# CAN_-_STM32F4.net
KiCad netlist of a schematic drawn in Altium Designer
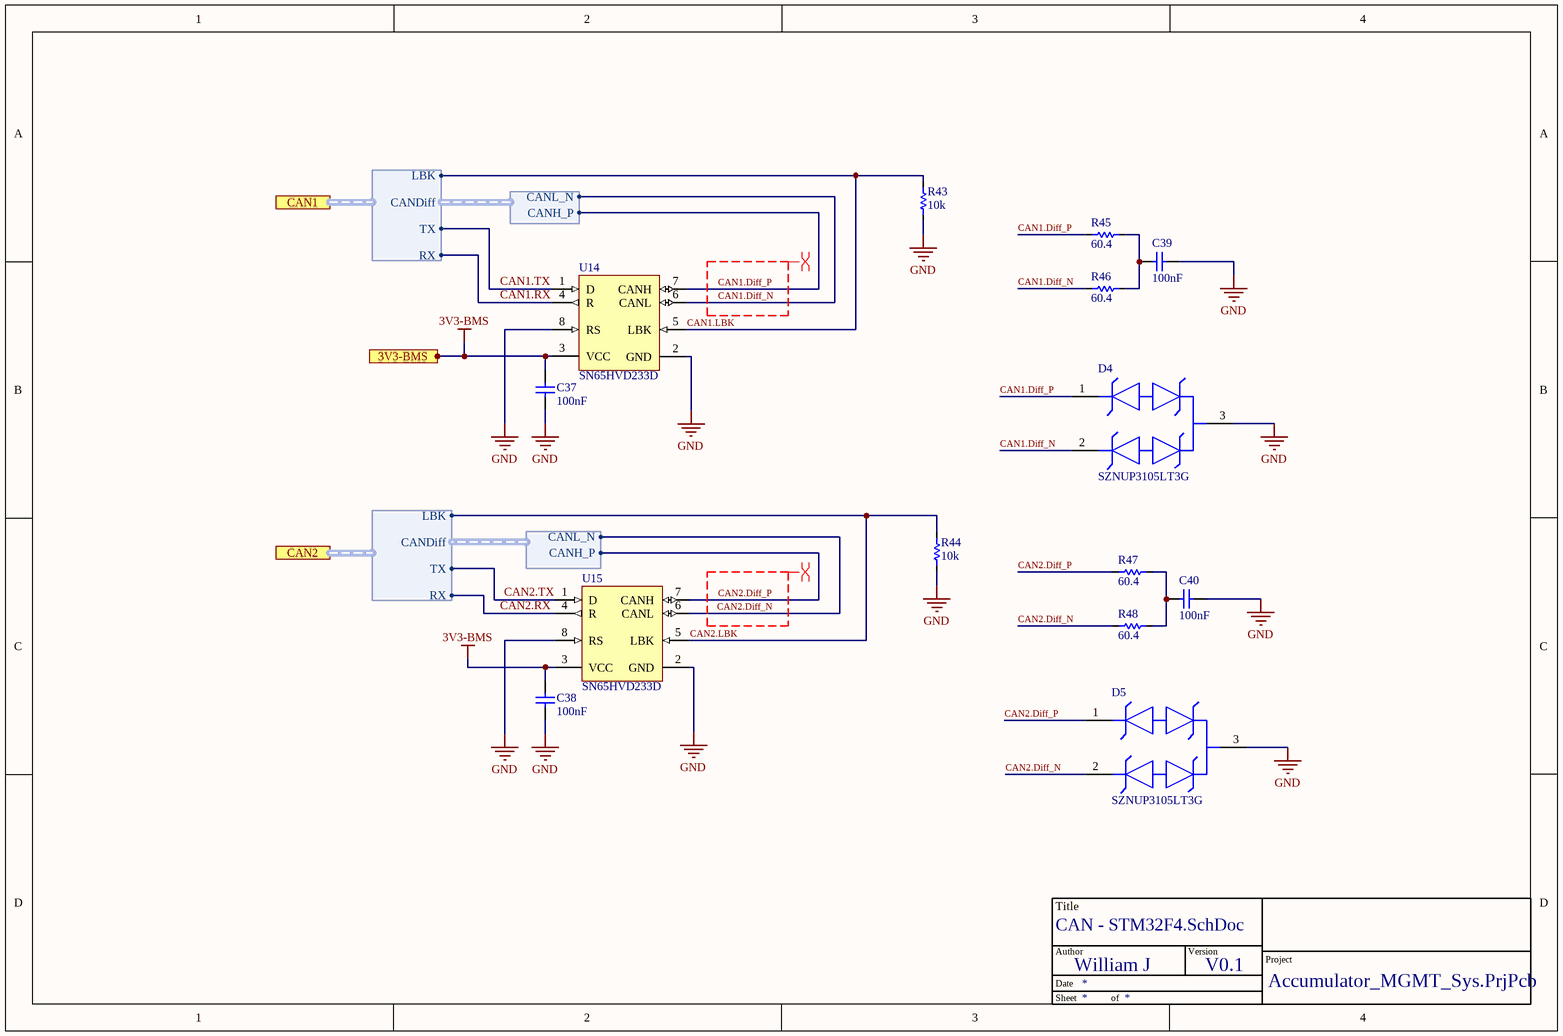
[diagram p0: CAN - STM32F4.SchDoc]

(export (version "E")
  (design (tool "Eeschema 10.0.6"))
  (components
    (comp (ref "C37")
      (value "100nF")
      (footprint "C_0603")
      (description "Capacitor")
      (fields (field (name "Comment") "C0603C104K3RAC7013"))
      (libsource (lib "Passives") (part "Capacitor"))
    )
    (comp (ref "C38")
      (value "100nF")
      (footprint "C_0603")
      (description "Capacitor")
      (fields (field (name "Comment") "C0603C104K3RAC7013"))
      (libsource (lib "Passives") (part "Capacitor"))
    )
    (comp (ref "C39")
      (value "100nF")
      (footprint "C_0603")
      (description "Capacitor")
      (fields (field (name "Comment") "C0603C104K3RAC7013"))
      (libsource (lib "Passives") (part "Capacitor"))
    )
    (comp (ref "C40")
      (value "100nF")
      (footprint "C_0603")
      (description "Capacitor")
      (fields (field (name "Comment") "C0603C104K3RAC7013"))
      (libsource (lib "Passives") (part "Capacitor"))
    )
    (comp (ref "D4")
      (value "SZNUP3105LT3G")
      (footprint "FP-318-08-MFG")
      (description "TVS DIODE 32V 66V SOT23-3")
      (fields
        (field (name "MANUFACTURER") "ON Semiconductor")
        (field (name "OCTOPART") "https://octopart.com/sznup3105lt3g-on+semiconductor-54318507")
      )
      (libsource (lib "Altium Content Vault") (part "ce38d3c06daa81fdde8c05c38ac5c9a"))
    )
    (comp (ref "D5")
      (value "SZNUP3105LT3G")
      (footprint "FP-318-08-MFG")
      (description "TVS DIODE 32V 66V SOT23-3")
      (fields
        (field (name "MANUFACTURER") "ON Semiconductor")
        (field (name "OCTOPART") "https://octopart.com/sznup3105lt3g-on+semiconductor-54318507")
      )
      (libsource (lib "Altium Content Vault") (part "ce38d3c06daa81fdde8c05c38ac5c9a"))
    )
    (comp (ref "R43")
      (value "10k")
      (footprint "R-0603")
      (description "Resistor")
      (fields (field (name "Comment") "RC0603FR-1310KL"))
      (libsource (lib "Passives") (part "Resistor"))
    )
    (comp (ref "R44")
      (value "10k")
      (footprint "R-0603")
      (description "Resistor")
      (fields (field (name "Comment") "RC0603FR-1310KL"))
      (libsource (lib "Passives") (part "Resistor"))
    )
    (comp (ref "R45")
      (value "60.4")
      (footprint "R-0603")
      (description "Resistor")
      (fields (field (name "Comment") "CRCW080560R4FKEA"))
      (libsource (lib "Passives") (part "Resistor"))
    )
    (comp (ref "R46")
      (value "60.4")
      (footprint "R-0603")
      (description "Resistor")
      (fields (field (name "Comment") "CRCW080560R4FKEA"))
      (libsource (lib "Passives") (part "Resistor"))
    )
    (comp (ref "R47")
      (value "60.4")
      (footprint "R-0603")
      (description "Resistor")
      (fields (field (name "Comment") "CRCW080560R4FKEA"))
      (libsource (lib "Passives") (part "Resistor"))
    )
    (comp (ref "R48")
      (value "60.4")
      (footprint "R-0603")
      (description "Resistor")
      (fields (field (name "Comment") "CRCW080560R4FKEA"))
      (libsource (lib "Passives") (part "Resistor"))
    )
    (comp (ref "U14")
      (value "SN65HVD233D")
      (footprint "D0008A_N")
      (fields (field (name "MANUFACTURER") "Texas Instruments"))
      (libsource (lib "") (part "TI-SN65HVD233-SOIC_D-8_1"))
    )
    (comp (ref "U15")
      (value "SN65HVD233D")
      (footprint "D0008A_N")
      (fields (field (name "MANUFACTURER") "Texas Instruments"))
      (libsource (lib "Altium Content Vault") (part "TI-SN65HVD233-SOIC_D-8"))
    )
  )
  (nets
    (net (code "3") (name "/CAN1.Diff_N") (class "Default")
      (node (ref "D4") (pin "2") (pinfunction "2_2") (pintype "passive"))
      (node (ref "R46") (pin "1") (pinfunction "1_1") (pintype "passive"))
      (node (ref "U14") (pin "6") (pinfunction "CANL_6") (pintype "bidirectional"))
    )
    (net (code "4") (name "/CAN1.Diff_P") (class "Default")
      (node (ref "D4") (pin "1") (pinfunction "1_1") (pintype "passive"))
      (node (ref "R45") (pin "1") (pinfunction "1_1") (pintype "passive"))
      (node (ref "U14") (pin "7") (pinfunction "CANH_7") (pintype "bidirectional"))
    )
    (net (code "5") (name "/CAN1.LBK") (class "Default")
      (node (ref "R43") (pin "2") (pinfunction "2_2") (pintype "passive"))
      (node (ref "U14") (pin "5") (pinfunction "LBK_5") (pintype "input"))
    )
    (net (code "6") (name "/CAN1.RX") (class "Default")
      (node (ref "U14") (pin "4") (pinfunction "R_4") (pintype "output"))
    )
    (net (code "7") (name "/CAN1.TX") (class "Default")
      (node (ref "U14") (pin "1") (pinfunction "D_1") (pintype "input"))
    )
    (net (code "8") (name "/CAN2.Diff_N") (class "Default")
      (node (ref "D5") (pin "2") (pinfunction "2_2") (pintype "passive"))
      (node (ref "R48") (pin "1") (pinfunction "1_1") (pintype "passive"))
      (node (ref "U15") (pin "6") (pinfunction "CANL_6") (pintype "bidirectional"))
    )
    (net (code "9") (name "/CAN2.Diff_P") (class "Default")
      (node (ref "D5") (pin "1") (pinfunction "1_1") (pintype "passive"))
      (node (ref "R47") (pin "1") (pinfunction "1_1") (pintype "passive"))
      (node (ref "U15") (pin "7") (pinfunction "CANH_7") (pintype "bidirectional"))
    )
    (net (code "10") (name "/CAN2.LBK") (class "Default")
      (node (ref "R44") (pin "2") (pinfunction "2_2") (pintype "passive"))
      (node (ref "U15") (pin "5") (pinfunction "LBK_5") (pintype "input"))
    )
    (net (code "11") (name "/CAN2.RX") (class "Default")
      (node (ref "U15") (pin "4") (pinfunction "R_4") (pintype "output"))
    )
    (net (code "12") (name "/CAN2.TX") (class "Default")
      (node (ref "U15") (pin "1") (pinfunction "D_1") (pintype "input"))
    )
    (net (code "15") (name "3V3-BMS") (class "Default")
      (node (ref "C37") (pin "2") (pinfunction "2_2") (pintype "passive"))
      (node (ref "C38") (pin "2") (pinfunction "2_2") (pintype "passive"))
      (node (ref "U14") (pin "3") (pinfunction "VCC_3") (pintype "passive"))
      (node (ref "U15") (pin "3") (pinfunction "VCC_3") (pintype "passive"))
    )
    (net (code "16") (name "GND") (class "Default")
      (node (ref "C37") (pin "1") (pinfunction "1_1") (pintype "passive"))
      (node (ref "C38") (pin "1") (pinfunction "1_1") (pintype "passive"))
      (node (ref "C39") (pin "1") (pinfunction "1_1") (pintype "passive"))
      (node (ref "C40") (pin "1") (pinfunction "1_1") (pintype "passive"))
      (node (ref "D4") (pin "3") (pinfunction "3_3") (pintype "passive"))
      (node (ref "D5") (pin "3") (pinfunction "3_3") (pintype "passive"))
      (node (ref "R43") (pin "1") (pinfunction "1_1") (pintype "passive"))
      (node (ref "R44") (pin "1") (pinfunction "1_1") (pintype "passive"))
      (node (ref "U14") (pin "2") (pinfunction "GND_2") (pintype "power_in"))
      (node (ref "U14") (pin "8") (pinfunction "RS_8") (pintype "input"))
      (node (ref "U15") (pin "2") (pinfunction "GND_2") (pintype "power_in"))
      (node (ref "U15") (pin "8") (pinfunction "RS_8") (pintype "input"))
    )
    (net (code "17") (name "Net-(C39-Pad2)") (class "Default")
      (node (ref "C39") (pin "2") (pinfunction "2_2") (pintype "passive"))
      (node (ref "R45") (pin "2") (pinfunction "2_2") (pintype "passive"))
      (node (ref "R46") (pin "2") (pinfunction "2_2") (pintype "passive"))
    )
    (net (code "18") (name "Net-(C40-Pad2)") (class "Default")
      (node (ref "C40") (pin "2") (pinfunction "2_2") (pintype "passive"))
      (node (ref "R47") (pin "2") (pinfunction "2_2") (pintype "passive"))
      (node (ref "R48") (pin "2") (pinfunction "2_2") (pintype "passive"))
    )
  )
)
